# 8825cape-V1_0.net
KiCad netlist of a schematic drawn in EAGLE
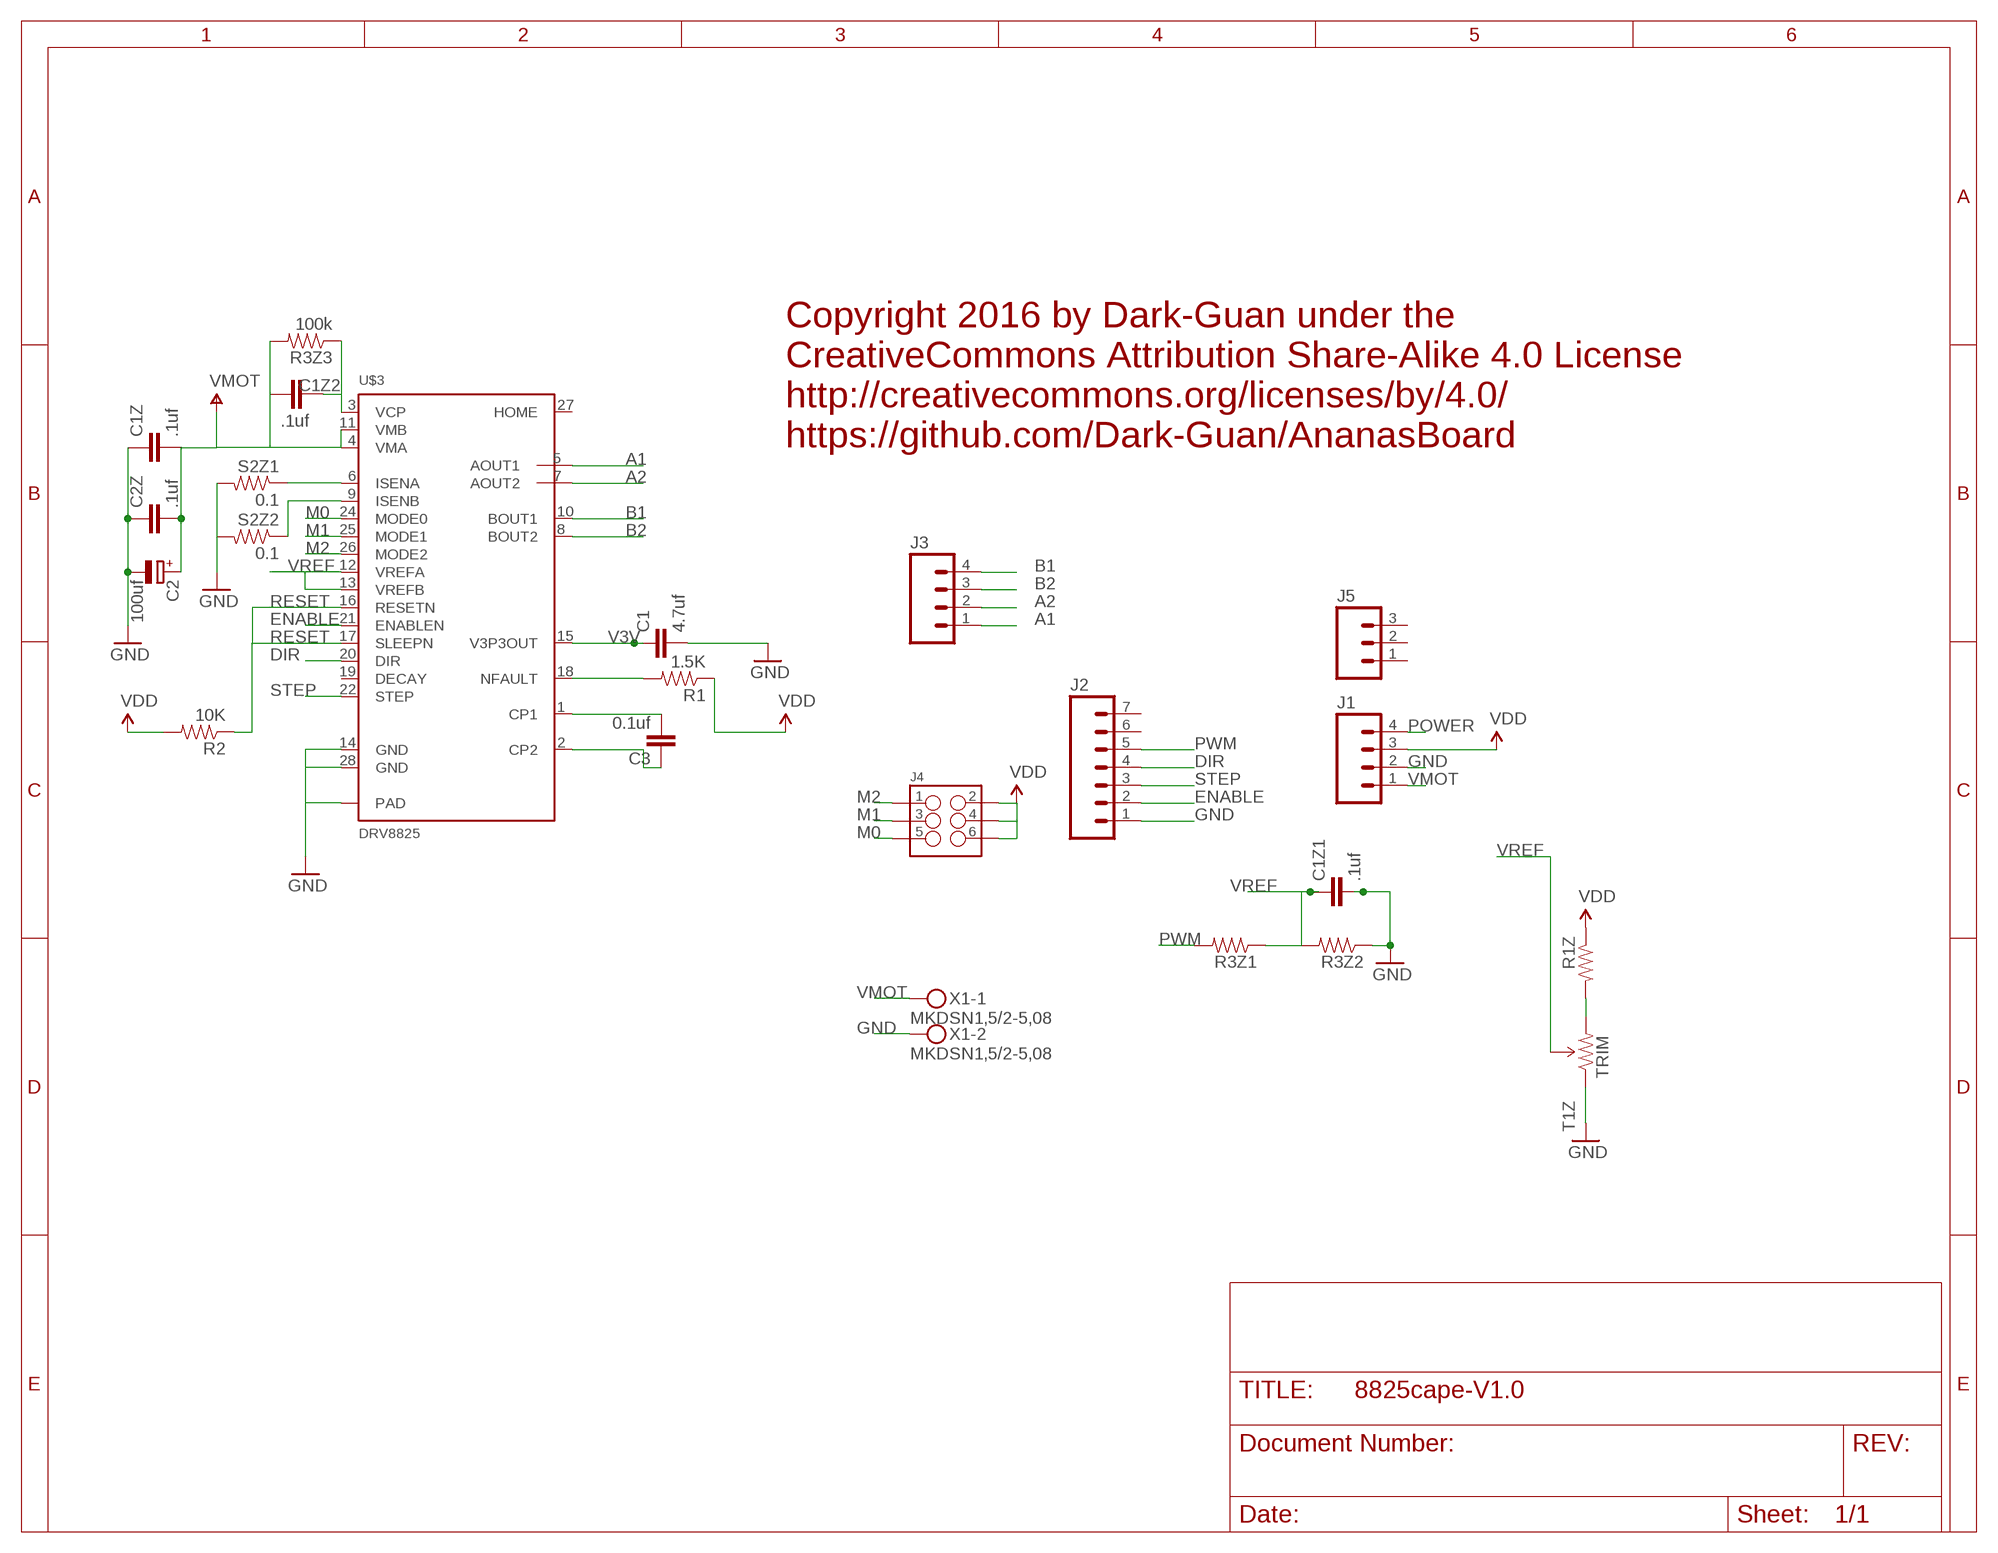
[diagram p0: schematic, sheet 1]

(export (version "E")
  (design (tool "Eeschema 10.0.6"))
  (components
    (comp (ref "C1")
      (value "4.7uf")
      (footprint "eagle-import:0402-CAP")
      (libsource (lib "eagle-import") (part "CAP0402-CAP"))
    )
    (comp (ref "C1Z")
      (value ".1uf")
      (footprint "eagle-import:0402-CAP")
      (libsource (lib "eagle-import") (part "CAP0402-CAP"))
    )
    (comp (ref "C1Z1")
      (value ".1uf")
      (footprint "eagle-import:0402-CAP")
      (libsource (lib "eagle-import") (part "CAP0402-CAP"))
    )
    (comp (ref "C1Z2")
      (value ".1uf")
      (footprint "eagle-import:0402-CAP")
      (libsource (lib "eagle-import") (part "CAP0402-CAP"))
    )
    (comp (ref "C2")
      (value "100uf")
      (footprint "eagle-import:153CLV-0605")
      (libsource (lib "eagle-import") (part "CPOL-EU153CLV-0605"))
    )
    (comp (ref "C2Z")
      (value ".1uf")
      (footprint "eagle-import:0402-CAP")
      (libsource (lib "eagle-import") (part "CAP0402-CAP"))
    )
    (comp (ref "C3")
      (value "0.1uf")
      (footprint "eagle-import:0402-CAP")
      (libsource (lib "eagle-import") (part "CAP0402-CAP"))
    )
    (comp (ref "J1")
      (value "M04PTH")
      (footprint "eagle-import:1X04")
      (libsource (lib "eagle-import") (part "M04PTH"))
    )
    (comp (ref "J2")
      (value "M07")
      (footprint "eagle-import:1X07")
      (libsource (lib "eagle-import") (part "M07"))
    )
    (comp (ref "J3")
      (value "M04PTH")
      (footprint "eagle-import:1X04")
      (libsource (lib "eagle-import") (part "M04PTH"))
    )
    (comp (ref "J4")
      (value "M03X2NO_SILK")
      (footprint "eagle-import:2X3-NS")
      (libsource (lib "eagle-import") (part "M03X2NO_SILK"))
    )
    (comp (ref "J5")
      (value "M03PTH")
      (footprint "eagle-import:1X03")
      (libsource (lib "eagle-import") (part "M03PTH"))
    )
    (comp (ref "R1")
      (value "1.5K")
      (footprint "eagle-import:0402-RES")
      (libsource (lib "eagle-import") (part "RESISTOR0402-RES"))
    )
    (comp (ref "R1Z")
      (value "RESISTOR0402-RES")
      (footprint "eagle-import:0402-RES")
      (libsource (lib "eagle-import") (part "RESISTOR0402-RES"))
    )
    (comp (ref "R2")
      (value "10K")
      (footprint "eagle-import:0402-RES")
      (libsource (lib "eagle-import") (part "RESISTOR0402-RES"))
    )
    (comp (ref "R3Z1")
      (value "RESISTOR0402-RES")
      (footprint "eagle-import:0402-RES")
      (libsource (lib "eagle-import") (part "RESISTOR0402-RES"))
    )
    (comp (ref "R3Z2")
      (value "RESISTOR0402-RES")
      (footprint "eagle-import:0402-RES")
      (libsource (lib "eagle-import") (part "RESISTOR0402-RES"))
    )
    (comp (ref "R3Z3")
      (value "100k")
      (footprint "eagle-import:0402-RES")
      (libsource (lib "eagle-import") (part "RESISTOR0402-RES"))
    )
    (comp (ref "S2Z1")
      (value "0.1")
      (footprint "eagle-import:0805")
      (libsource (lib "eagle-import") (part "RESISTOR"))
    )
    (comp (ref "S2Z2")
      (value "0.1")
      (footprint "eagle-import:0805")
      (libsource (lib "eagle-import") (part "RESISTOR"))
    )
    (comp (ref "T1Z")
      (value "TRIM")
      (footprint "eagle-import:TRIMPOT-3MM")
      (libsource (lib "eagle-import") (part "TRIMPOTSMD"))
    )
    (comp (ref "U$3")
      (value "DRV8825")
      (footprint "eagle-import:HTSSOP28")
      (libsource (lib "eagle-import") (part "DRV8825"))
    )
    (comp (ref "X1")
      (value "MKDSN1,5/2-5,08")
      (footprint "eagle-import:MKDSN1,5_2-5,08")
      (libsource (lib "eagle-import") (part "MKDSN1,5/2-5,08"))
    )
  )
  (nets
    (net (code "1") (name "/A1") (class "Default")
      (node (ref "J3") (pin "1") (pinfunction "1_1") (pintype "passive"))
      (node (ref "U$3") (pin "5") (pinfunction "AOUT1_5") (pintype "bidirectional"))
    )
    (net (code "2") (name "/A2") (class "Default")
      (node (ref "J3") (pin "2") (pinfunction "2_2") (pintype "passive"))
      (node (ref "U$3") (pin "7") (pinfunction "AOUT2_7") (pintype "bidirectional"))
    )
    (net (code "3") (name "/B1") (class "Default")
      (node (ref "J3") (pin "4") (pinfunction "4_4") (pintype "passive"))
      (node (ref "U$3") (pin "10") (pinfunction "BOUT1_10") (pintype "bidirectional"))
    )
    (net (code "4") (name "/B2") (class "Default")
      (node (ref "J3") (pin "3") (pinfunction "3_3") (pintype "passive"))
      (node (ref "U$3") (pin "8") (pinfunction "BOUT2_8") (pintype "bidirectional"))
    )
    (net (code "5") (name "/DIR") (class "Default")
      (node (ref "J2") (pin "4") (pinfunction "4_4") (pintype "passive"))
      (node (ref "U$3") (pin "20") (pinfunction "DIR_20") (pintype "bidirectional"))
    )
    (net (code "6") (name "/ENABLE") (class "Default")
      (node (ref "J2") (pin "2") (pinfunction "2_2") (pintype "passive"))
      (node (ref "U$3") (pin "21") (pinfunction "ENABLEN_21") (pintype "bidirectional"))
    )
    (net (code "7") (name "/M0") (class "Default")
      (node (ref "J4") (pin "5") (pinfunction "5_5") (pintype "bidirectional"))
      (node (ref "U$3") (pin "24") (pinfunction "MODE0_24") (pintype "bidirectional"))
    )
    (net (code "8") (name "/M1") (class "Default")
      (node (ref "J4") (pin "3") (pinfunction "3_3") (pintype "bidirectional"))
      (node (ref "U$3") (pin "25") (pinfunction "MODE1_25") (pintype "bidirectional"))
    )
    (net (code "9") (name "/M2") (class "Default")
      (node (ref "J4") (pin "1") (pinfunction "1_1") (pintype "bidirectional"))
      (node (ref "U$3") (pin "26") (pinfunction "MODE2_26") (pintype "bidirectional"))
    )
    (net (code "10") (name "/POWER") (class "Default")
      (node (ref "J1") (pin "4") (pinfunction "4_4") (pintype "passive"))
    )
    (net (code "11") (name "/PWM") (class "Default")
      (node (ref "J2") (pin "5") (pinfunction "5_5") (pintype "passive"))
      (node (ref "R3Z1") (pin "2") (pinfunction "2_2") (pintype "passive"))
    )
    (net (code "12") (name "/RESET") (class "Default")
      (node (ref "R2") (pin "1") (pinfunction "1_1") (pintype "passive"))
      (node (ref "U$3") (pin "16") (pinfunction "RESETN_16") (pintype "bidirectional"))
      (node (ref "U$3") (pin "17") (pinfunction "SLEEPN_17") (pintype "bidirectional"))
    )
    (net (code "13") (name "/STEP") (class "Default")
      (node (ref "J2") (pin "3") (pinfunction "3_3") (pintype "passive"))
      (node (ref "U$3") (pin "22") (pinfunction "STEP_22") (pintype "bidirectional"))
    )
    (net (code "14") (name "/V3V") (class "Default")
      (node (ref "C1") (pin "1") (pinfunction "1_1") (pintype "passive"))
      (node (ref "U$3") (pin "15") (pinfunction "V3P3OUT_15") (pintype "bidirectional"))
    )
    (net (code "15") (name "/VREF") (class "Default")
      (node (ref "C1Z1") (pin "1") (pinfunction "1_1") (pintype "passive"))
      (node (ref "R3Z1") (pin "1") (pinfunction "1_1") (pintype "passive"))
      (node (ref "R3Z2") (pin "2") (pinfunction "2_2") (pintype "passive"))
      (node (ref "T1Z") (pin "2") (pinfunction "WIPER_2") (pintype "passive"))
      (node (ref "U$3") (pin "12") (pinfunction "VREFA_12") (pintype "bidirectional"))
      (node (ref "U$3") (pin "13") (pinfunction "VREFB_13") (pintype "bidirectional"))
    )
    (net (code "16") (name "GND") (class "Default")
      (node (ref "C1") (pin "2") (pinfunction "2_2") (pintype "passive"))
      (node (ref "C1Z") (pin "1") (pinfunction "1_1") (pintype "passive"))
      (node (ref "C1Z1") (pin "2") (pinfunction "2_2") (pintype "passive"))
      (node (ref "C2") (pin "-") (pinfunction "-_-") (pintype "passive"))
      (node (ref "C2Z") (pin "1") (pinfunction "1_1") (pintype "passive"))
      (node (ref "J1") (pin "2") (pinfunction "2_2") (pintype "passive"))
      (node (ref "J2") (pin "1") (pinfunction "1_1") (pintype "passive"))
      (node (ref "R3Z2") (pin "1") (pinfunction "1_1") (pintype "passive"))
      (node (ref "S2Z1") (pin "2") (pinfunction "2_2") (pintype "passive"))
      (node (ref "S2Z2") (pin "2") (pinfunction "2_2") (pintype "passive"))
      (node (ref "T1Z") (pin "1") (pinfunction "CCW_1") (pintype "passive"))
      (node (ref "U$3") (pin "14") (pinfunction "GND_14") (pintype "bidirectional"))
      (node (ref "U$3") (pin "28") (pinfunction "GND_28") (pintype "bidirectional"))
      (node (ref "U$3") (pin "GND@10") (pinfunction "PAD_GND@10") (pintype "bidirectional"))
      (node (ref "U$3") (pin "GND@11") (pinfunction "PAD_GND@11") (pintype "bidirectional"))
      (node (ref "U$3") (pin "GND@12") (pinfunction "PAD_GND@12") (pintype "bidirectional"))
      (node (ref "U$3") (pin "GND@13") (pinfunction "PAD_GND@13") (pintype "bidirectional"))
      (node (ref "U$3") (pin "GND@14") (pinfunction "PAD_GND@14") (pintype "bidirectional"))
      (node (ref "U$3") (pin "GND@15") (pinfunction "PAD_GND@15") (pintype "bidirectional"))
      (node (ref "U$3") (pin "GND@16") (pinfunction "PAD_GND@16") (pintype "bidirectional"))
      (node (ref "U$3") (pin "GND@17") (pinfunction "PAD_GND@17") (pintype "bidirectional"))
      (node (ref "U$3") (pin "GND@18") (pinfunction "PAD_GND@18") (pintype "bidirectional"))
      (node (ref "U$3") (pin "GND@19") (pinfunction "PAD_GND@19") (pintype "bidirectional"))
      (node (ref "U$3") (pin "GND@20") (pinfunction "PAD_GND@20") (pintype "bidirectional"))
      (node (ref "U$3") (pin "GND@21") (pinfunction "PAD_GND@21") (pintype "bidirectional"))
      (node (ref "U$3") (pin "GND@22") (pinfunction "PAD_GND@22") (pintype "bidirectional"))
      (node (ref "U$3") (pin "GND@23") (pinfunction "PAD_GND@23") (pintype "bidirectional"))
      (node (ref "U$3") (pin "GND@24") (pinfunction "PAD_GND@24") (pintype "bidirectional"))
      (node (ref "U$3") (pin "GND@25") (pinfunction "PAD_GND@25") (pintype "bidirectional"))
      (node (ref "U$3") (pin "GND@26") (pinfunction "PAD_GND@26") (pintype "bidirectional"))
      (node (ref "U$3") (pin "GND@27") (pinfunction "PAD_GND@27") (pintype "bidirectional"))
      (node (ref "U$3") (pin "GND@28") (pinfunction "PAD_GND@28") (pintype "bidirectional"))
      (node (ref "U$3") (pin "GND@29") (pinfunction "PAD_GND@29") (pintype "bidirectional"))
      (node (ref "U$3") (pin "GND@30") (pinfunction "PAD_GND@30") (pintype "bidirectional"))
      (node (ref "U$3") (pin "GND@PAD") (pinfunction "PAD_GND@PAD") (pintype "bidirectional"))
      (node (ref "X1") (pin "2") (pinfunction "KL_2") (pintype "passive"))
    )
    (net (code "17") (name "Net-(T1Z-CW)") (class "Default")
      (node (ref "R1Z") (pin "2") (pinfunction "2_2") (pintype "passive"))
      (node (ref "T1Z") (pin "3") (pinfunction "CW_3") (pintype "passive"))
    )
    (net (code "18") (name "Net-(U$3-CP1)") (class "Default")
      (node (ref "C3") (pin "2") (pinfunction "2_2") (pintype "passive"))
      (node (ref "U$3") (pin "1") (pinfunction "CP1_1") (pintype "bidirectional"))
    )
    (net (code "19") (name "Net-(U$3-CP2)") (class "Default")
      (node (ref "C3") (pin "1") (pinfunction "1_1") (pintype "passive"))
      (node (ref "U$3") (pin "2") (pinfunction "CP2_2") (pintype "bidirectional"))
    )
    (net (code "20") (name "Net-(U$3-ISENA)") (class "Default")
      (node (ref "S2Z1") (pin "1") (pinfunction "1_1") (pintype "passive"))
      (node (ref "U$3") (pin "6") (pinfunction "ISENA_6") (pintype "bidirectional"))
    )
    (net (code "21") (name "Net-(U$3-ISENB)") (class "Default")
      (node (ref "S2Z2") (pin "1") (pinfunction "1_1") (pintype "passive"))
      (node (ref "U$3") (pin "9") (pinfunction "ISENB_9") (pintype "bidirectional"))
    )
    (net (code "22") (name "Net-(U$3-NFAULT)") (class "Default")
      (node (ref "R1") (pin "2") (pinfunction "2_2") (pintype "passive"))
      (node (ref "U$3") (pin "18") (pinfunction "NFAULT_18") (pintype "bidirectional"))
    )
    (net (code "23") (name "Net-(U$3-VCP)") (class "Default")
      (node (ref "C1Z2") (pin "1") (pinfunction "1_1") (pintype "passive"))
      (node (ref "R3Z3") (pin "1") (pinfunction "1_1") (pintype "passive"))
      (node (ref "U$3") (pin "3") (pinfunction "VCP_3") (pintype "bidirectional"))
    )
    (net (code "24") (name "VDD") (class "Default")
      (node (ref "J1") (pin "3") (pinfunction "3_3") (pintype "passive"))
      (node (ref "J4") (pin "2") (pinfunction "2_2") (pintype "bidirectional"))
      (node (ref "J4") (pin "4") (pinfunction "4_4") (pintype "bidirectional"))
      (node (ref "J4") (pin "6") (pinfunction "6_6") (pintype "bidirectional"))
      (node (ref "R1") (pin "1") (pinfunction "1_1") (pintype "passive"))
      (node (ref "R1Z") (pin "1") (pinfunction "1_1") (pintype "passive"))
      (node (ref "R2") (pin "2") (pinfunction "2_2") (pintype "passive"))
    )
    (net (code "25") (name "VMOT") (class "Default")
      (node (ref "C1Z") (pin "2") (pinfunction "2_2") (pintype "passive"))
      (node (ref "C1Z2") (pin "2") (pinfunction "2_2") (pintype "passive"))
      (node (ref "C2") (pin "+") (pinfunction "+_+") (pintype "passive"))
      (node (ref "C2Z") (pin "2") (pinfunction "2_2") (pintype "passive"))
      (node (ref "J1") (pin "1") (pinfunction "1_1") (pintype "passive"))
      (node (ref "R3Z3") (pin "2") (pinfunction "2_2") (pintype "passive"))
      (node (ref "U$3") (pin "11") (pinfunction "VMB_11") (pintype "bidirectional"))
      (node (ref "U$3") (pin "4") (pinfunction "VMA_4") (pintype "bidirectional"))
      (node (ref "X1") (pin "1") (pinfunction "KL_1") (pintype "passive"))
    )
    (net (code "26") (name "unconnected-(J2-Pad6)") (class "Default")
      (node (ref "J2") (pin "6") (pinfunction "6_6") (pintype "passive"))
    )
    (net (code "27") (name "unconnected-(J2-Pad7)") (class "Default")
      (node (ref "J2") (pin "7") (pinfunction "7_7") (pintype "passive"))
    )
    (net (code "28") (name "unconnected-(J5-Pad1)") (class "Default")
      (node (ref "J5") (pin "1") (pinfunction "1_1") (pintype "passive"))
    )
    (net (code "29") (name "unconnected-(J5-Pad2)") (class "Default")
      (node (ref "J5") (pin "2") (pinfunction "2_2") (pintype "passive"))
    )
    (net (code "30") (name "unconnected-(J5-Pad3)") (class "Default")
      (node (ref "J5") (pin "3") (pinfunction "3_3") (pintype "passive"))
    )
    (net (code "31") (name "unconnected-(U$3-DECAY-Pad19)") (class "Default")
      (node (ref "U$3") (pin "19") (pinfunction "DECAY_19") (pintype "bidirectional"))
    )
    (net (code "32") (name "unconnected-(U$3-HOME-Pad27)") (class "Default")
      (node (ref "U$3") (pin "27") (pinfunction "HOME_27") (pintype "bidirectional"))
    )
  )
)
